# Counters.net
KiCad netlist of a schematic drawn in Altium Designer
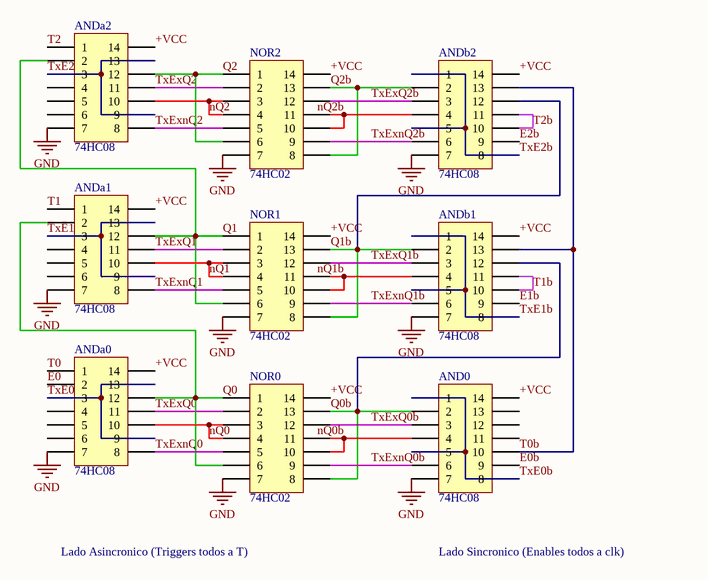
[diagram p0: Counters.SchDoc]

(export (version "E")
  (design (tool "Eeschema 10.0.6"))
  (components
    (comp (ref "AND0") (value "74HC08") (footprint "DIP14") (libsource (lib "LIBEBAL") (part "IC_DIP14")))
    (comp (ref "ANDa0") (value "74HC08") (footprint "DIP14") (libsource (lib "LIBEBAL") (part "IC_DIP14")))
    (comp (ref "ANDa1") (value "74HC08") (footprint "DIP14") (libsource (lib "LIBEBAL") (part "IC_DIP14")))
    (comp (ref "ANDa2") (value "74HC08") (footprint "DIP14") (libsource (lib "LIBEBAL") (part "IC_DIP14")))
    (comp (ref "ANDb1") (value "74HC08") (footprint "DIP14") (libsource (lib "LIBEBAL") (part "IC_DIP14")))
    (comp (ref "ANDb2") (value "74HC08") (footprint "DIP14") (libsource (lib "LIBEBAL") (part "IC_DIP14")))
    (comp (ref "NOR0") (value "74HC02") (footprint "DIP14") (libsource (lib "LIBEBAL") (part "IC_DIP14")))
    (comp (ref "NOR1") (value "74HC02") (footprint "DIP14") (libsource (lib "LIBEBAL") (part "IC_DIP14")))
    (comp (ref "NOR2") (value "74HC02") (footprint "DIP14") (libsource (lib "LIBEBAL") (part "IC_DIP14")))
  )
  (nets
    (net (code "1") (name "/+VCC") (class "Default")
      (node (ref "AND0") (pin "14") (pinfunction "14_14") (pintype "passive"))
      (node (ref "ANDa0") (pin "14") (pinfunction "14_14") (pintype "passive"))
      (node (ref "ANDa1") (pin "14") (pinfunction "14_14") (pintype "passive"))
      (node (ref "ANDa2") (pin "14") (pinfunction "14_14") (pintype "passive"))
      (node (ref "ANDb1") (pin "14") (pinfunction "14_14") (pintype "passive"))
      (node (ref "ANDb2") (pin "14") (pinfunction "14_14") (pintype "passive"))
      (node (ref "NOR0") (pin "14") (pinfunction "14_14") (pintype "passive"))
      (node (ref "NOR1") (pin "14") (pinfunction "14_14") (pintype "passive"))
      (node (ref "NOR2") (pin "14") (pinfunction "14_14") (pintype "passive"))
    )
    (net (code "2") (name "/E0") (class "Default")
      (node (ref "ANDa0") (pin "2") (pinfunction "2_2") (pintype "passive"))
    )
    (net (code "3") (name "/E0b") (class "Default")
      (node (ref "AND0") (pin "9") (pinfunction "9_9") (pintype "passive"))
    )
    (net (code "4") (name "/E1b") (class "Default")
      (node (ref "ANDb1") (pin "9") (pinfunction "9_9") (pintype "passive"))
    )
    (net (code "5") (name "/E2b") (class "Default")
      (node (ref "ANDb2") (pin "9") (pinfunction "9_9") (pintype "passive"))
    )
    (net (code "6") (name "/Q0") (class "Default")
      (node (ref "ANDa0") (pin "12") (pinfunction "12_12") (pintype "passive"))
      (node (ref "ANDa1") (pin "2") (pinfunction "2_2") (pintype "passive"))
      (node (ref "NOR0") (pin "1") (pinfunction "1_1") (pintype "passive"))
      (node (ref "NOR0") (pin "6") (pinfunction "6_6") (pintype "passive"))
    )
    (net (code "7") (name "/Q0b") (class "Default")
      (node (ref "AND0") (pin "2") (pinfunction "2_2") (pintype "passive"))
      (node (ref "ANDb1") (pin "12") (pinfunction "12_12") (pintype "passive"))
      (node (ref "NOR0") (pin "13") (pinfunction "13_13") (pintype "passive"))
      (node (ref "NOR0") (pin "8") (pinfunction "8_8") (pintype "passive"))
    )
    (net (code "8") (name "/Q1") (class "Default")
      (node (ref "ANDa1") (pin "12") (pinfunction "12_12") (pintype "passive"))
      (node (ref "ANDa2") (pin "2") (pinfunction "2_2") (pintype "passive"))
      (node (ref "NOR1") (pin "1") (pinfunction "1_1") (pintype "passive"))
      (node (ref "NOR1") (pin "6") (pinfunction "6_6") (pintype "passive"))
    )
    (net (code "9") (name "/Q1b") (class "Default")
      (node (ref "ANDb1") (pin "2") (pinfunction "2_2") (pintype "passive"))
      (node (ref "ANDb2") (pin "12") (pinfunction "12_12") (pintype "passive"))
      (node (ref "NOR1") (pin "13") (pinfunction "13_13") (pintype "passive"))
      (node (ref "NOR1") (pin "8") (pinfunction "8_8") (pintype "passive"))
    )
    (net (code "10") (name "/Q2") (class "Default")
      (node (ref "ANDa2") (pin "12") (pinfunction "12_12") (pintype "passive"))
      (node (ref "NOR2") (pin "1") (pinfunction "1_1") (pintype "passive"))
      (node (ref "NOR2") (pin "6") (pinfunction "6_6") (pintype "passive"))
    )
    (net (code "11") (name "/Q2b") (class "Default")
      (node (ref "ANDb2") (pin "2") (pinfunction "2_2") (pintype "passive"))
      (node (ref "NOR2") (pin "13") (pinfunction "13_13") (pintype "passive"))
      (node (ref "NOR2") (pin "8") (pinfunction "8_8") (pintype "passive"))
    )
    (net (code "12") (name "/T0") (class "Default")
      (node (ref "ANDa0") (pin "1") (pinfunction "1_1") (pintype "passive"))
    )
    (net (code "13") (name "/T0b") (class "Default")
      (node (ref "AND0") (pin "10") (pinfunction "10_10") (pintype "passive"))
      (node (ref "ANDb1") (pin "13") (pinfunction "13_13") (pintype "passive"))
      (node (ref "ANDb2") (pin "13") (pinfunction "13_13") (pintype "passive"))
    )
    (net (code "14") (name "/T1") (class "Default")
      (node (ref "ANDa1") (pin "1") (pinfunction "1_1") (pintype "passive"))
    )
    (net (code "15") (name "/T1b") (class "Default")
      (node (ref "ANDb1") (pin "10") (pinfunction "10_10") (pintype "passive"))
      (node (ref "ANDb1") (pin "11") (pinfunction "11_11") (pintype "passive"))
    )
    (net (code "16") (name "/T2") (class "Default")
      (node (ref "ANDa2") (pin "1") (pinfunction "1_1") (pintype "passive"))
    )
    (net (code "17") (name "/T2b") (class "Default")
      (node (ref "ANDb2") (pin "10") (pinfunction "10_10") (pintype "passive"))
      (node (ref "ANDb2") (pin "11") (pinfunction "11_11") (pintype "passive"))
    )
    (net (code "18") (name "/TxE0") (class "Default")
      (node (ref "ANDa0") (pin "13") (pinfunction "13_13") (pintype "passive"))
      (node (ref "ANDa0") (pin "3") (pinfunction "3_3") (pintype "passive"))
      (node (ref "ANDa0") (pin "9") (pinfunction "9_9") (pintype "passive"))
    )
    (net (code "19") (name "/TxE0b") (class "Default")
      (node (ref "AND0") (pin "1") (pinfunction "1_1") (pintype "passive"))
      (node (ref "AND0") (pin "5") (pinfunction "5_5") (pintype "passive"))
      (node (ref "AND0") (pin "8") (pinfunction "8_8") (pintype "passive"))
    )
    (net (code "20") (name "/TxE1") (class "Default")
      (node (ref "ANDa1") (pin "13") (pinfunction "13_13") (pintype "passive"))
      (node (ref "ANDa1") (pin "3") (pinfunction "3_3") (pintype "passive"))
      (node (ref "ANDa1") (pin "9") (pinfunction "9_9") (pintype "passive"))
    )
    (net (code "21") (name "/TxE1b") (class "Default")
      (node (ref "ANDb1") (pin "1") (pinfunction "1_1") (pintype "passive"))
      (node (ref "ANDb1") (pin "5") (pinfunction "5_5") (pintype "passive"))
      (node (ref "ANDb1") (pin "8") (pinfunction "8_8") (pintype "passive"))
    )
    (net (code "22") (name "/TxE2") (class "Default")
      (node (ref "ANDa2") (pin "13") (pinfunction "13_13") (pintype "passive"))
      (node (ref "ANDa2") (pin "3") (pinfunction "3_3") (pintype "passive"))
      (node (ref "ANDa2") (pin "9") (pinfunction "9_9") (pintype "passive"))
    )
    (net (code "23") (name "/TxE2b") (class "Default")
      (node (ref "ANDb2") (pin "1") (pinfunction "1_1") (pintype "passive"))
      (node (ref "ANDb2") (pin "5") (pinfunction "5_5") (pintype "passive"))
      (node (ref "ANDb2") (pin "8") (pinfunction "8_8") (pintype "passive"))
    )
    (net (code "24") (name "/TxExQ0") (class "Default")
      (node (ref "ANDa0") (pin "11") (pinfunction "11_11") (pintype "passive"))
      (node (ref "NOR0") (pin "2") (pinfunction "2_2") (pintype "passive"))
    )
    (net (code "25") (name "/TxExQ0b") (class "Default")
      (node (ref "AND0") (pin "3") (pinfunction "3_3") (pintype "passive"))
      (node (ref "NOR0") (pin "12") (pinfunction "12_12") (pintype "passive"))
    )
    (net (code "26") (name "/TxExQ1") (class "Default")
      (node (ref "ANDa1") (pin "11") (pinfunction "11_11") (pintype "passive"))
      (node (ref "NOR1") (pin "2") (pinfunction "2_2") (pintype "passive"))
    )
    (net (code "27") (name "/TxExQ1b") (class "Default")
      (node (ref "ANDb1") (pin "3") (pinfunction "3_3") (pintype "passive"))
      (node (ref "NOR1") (pin "12") (pinfunction "12_12") (pintype "passive"))
    )
    (net (code "28") (name "/TxExQ2") (class "Default")
      (node (ref "ANDa2") (pin "11") (pinfunction "11_11") (pintype "passive"))
      (node (ref "NOR2") (pin "2") (pinfunction "2_2") (pintype "passive"))
    )
    (net (code "29") (name "/TxExQ2b") (class "Default")
      (node (ref "ANDb2") (pin "3") (pinfunction "3_3") (pintype "passive"))
      (node (ref "NOR2") (pin "12") (pinfunction "12_12") (pintype "passive"))
    )
    (net (code "30") (name "/TxExnQ0") (class "Default")
      (node (ref "ANDa0") (pin "8") (pinfunction "8_8") (pintype "passive"))
      (node (ref "NOR0") (pin "5") (pinfunction "5_5") (pintype "passive"))
    )
    (net (code "31") (name "/TxExnQ0b") (class "Default")
      (node (ref "AND0") (pin "6") (pinfunction "6_6") (pintype "passive"))
      (node (ref "NOR0") (pin "9") (pinfunction "9_9") (pintype "passive"))
    )
    (net (code "32") (name "/TxExnQ1") (class "Default")
      (node (ref "ANDa1") (pin "8") (pinfunction "8_8") (pintype "passive"))
      (node (ref "NOR1") (pin "5") (pinfunction "5_5") (pintype "passive"))
    )
    (net (code "33") (name "/TxExnQ1b") (class "Default")
      (node (ref "ANDb1") (pin "6") (pinfunction "6_6") (pintype "passive"))
      (node (ref "NOR1") (pin "9") (pinfunction "9_9") (pintype "passive"))
    )
    (net (code "34") (name "/TxExnQ2") (class "Default")
      (node (ref "ANDa2") (pin "8") (pinfunction "8_8") (pintype "passive"))
      (node (ref "NOR2") (pin "5") (pinfunction "5_5") (pintype "passive"))
    )
    (net (code "35") (name "/TxExnQ2b") (class "Default")
      (node (ref "ANDb2") (pin "6") (pinfunction "6_6") (pintype "passive"))
      (node (ref "NOR2") (pin "9") (pinfunction "9_9") (pintype "passive"))
    )
    (net (code "36") (name "/nQ0") (class "Default")
      (node (ref "ANDa0") (pin "10") (pinfunction "10_10") (pintype "passive"))
      (node (ref "NOR0") (pin "3") (pinfunction "3_3") (pintype "passive"))
      (node (ref "NOR0") (pin "4") (pinfunction "4_4") (pintype "passive"))
    )
    (net (code "38") (name "/nQ1") (class "Default")
      (node (ref "ANDa1") (pin "10") (pinfunction "10_10") (pintype "passive"))
      (node (ref "NOR1") (pin "3") (pinfunction "3_3") (pintype "passive"))
      (node (ref "NOR1") (pin "4") (pinfunction "4_4") (pintype "passive"))
    )
    (net (code "40") (name "/nQ2") (class "Default")
      (node (ref "ANDa2") (pin "10") (pinfunction "10_10") (pintype "passive"))
      (node (ref "NOR2") (pin "3") (pinfunction "3_3") (pintype "passive"))
      (node (ref "NOR2") (pin "4") (pinfunction "4_4") (pintype "passive"))
    )
    (net (code "42") (name "GND") (class "Default")
      (node (ref "AND0") (pin "7") (pinfunction "7_7") (pintype "passive"))
      (node (ref "ANDa0") (pin "7") (pinfunction "7_7") (pintype "passive"))
      (node (ref "ANDa1") (pin "7") (pinfunction "7_7") (pintype "passive"))
      (node (ref "ANDa2") (pin "7") (pinfunction "7_7") (pintype "passive"))
      (node (ref "ANDb1") (pin "7") (pinfunction "7_7") (pintype "passive"))
      (node (ref "ANDb2") (pin "7") (pinfunction "7_7") (pintype "passive"))
      (node (ref "NOR0") (pin "7") (pinfunction "7_7") (pintype "passive"))
      (node (ref "NOR1") (pin "7") (pinfunction "7_7") (pintype "passive"))
      (node (ref "NOR2") (pin "7") (pinfunction "7_7") (pintype "passive"))
    )
    (net (code "43") (name "Net-(AND0-Pad4)") (class "Default")
      (node (ref "AND0") (pin "4") (pinfunction "4_4") (pintype "passive"))
      (node (ref "NOR0") (pin "10") (pinfunction "10_10") (pintype "passive"))
      (node (ref "NOR0") (pin "11") (pinfunction "11_11") (pintype "passive"))
    )
    (net (code "44") (name "Net-(ANDb1-Pad4)") (class "Default")
      (node (ref "ANDb1") (pin "4") (pinfunction "4_4") (pintype "passive"))
      (node (ref "NOR1") (pin "10") (pinfunction "10_10") (pintype "passive"))
      (node (ref "NOR1") (pin "11") (pinfunction "11_11") (pintype "passive"))
    )
    (net (code "45") (name "Net-(ANDb2-Pad4)") (class "Default")
      (node (ref "ANDb2") (pin "4") (pinfunction "4_4") (pintype "passive"))
      (node (ref "NOR2") (pin "10") (pinfunction "10_10") (pintype "passive"))
      (node (ref "NOR2") (pin "11") (pinfunction "11_11") (pintype "passive"))
    )
    (net (code "46") (name "unconnected-(AND0-Pad11)") (class "Default")
      (node (ref "AND0") (pin "11") (pinfunction "11_11") (pintype "passive"))
    )
    (net (code "47") (name "unconnected-(AND0-Pad12)") (class "Default")
      (node (ref "AND0") (pin "12") (pinfunction "12_12") (pintype "passive"))
    )
    (net (code "48") (name "unconnected-(AND0-Pad13)") (class "Default")
      (node (ref "AND0") (pin "13") (pinfunction "13_13") (pintype "passive"))
    )
    (net (code "49") (name "unconnected-(ANDa0-Pad4)") (class "Default")
      (node (ref "ANDa0") (pin "4") (pinfunction "4_4") (pintype "passive"))
    )
    (net (code "50") (name "unconnected-(ANDa0-Pad5)") (class "Default")
      (node (ref "ANDa0") (pin "5") (pinfunction "5_5") (pintype "passive"))
    )
    (net (code "51") (name "unconnected-(ANDa0-Pad6)") (class "Default")
      (node (ref "ANDa0") (pin "6") (pinfunction "6_6") (pintype "passive"))
    )
    (net (code "52") (name "unconnected-(ANDa1-Pad4)") (class "Default")
      (node (ref "ANDa1") (pin "4") (pinfunction "4_4") (pintype "passive"))
    )
    (net (code "53") (name "unconnected-(ANDa1-Pad5)") (class "Default")
      (node (ref "ANDa1") (pin "5") (pinfunction "5_5") (pintype "passive"))
    )
    (net (code "54") (name "unconnected-(ANDa1-Pad6)") (class "Default")
      (node (ref "ANDa1") (pin "6") (pinfunction "6_6") (pintype "passive"))
    )
    (net (code "55") (name "unconnected-(ANDa2-Pad4)") (class "Default")
      (node (ref "ANDa2") (pin "4") (pinfunction "4_4") (pintype "passive"))
    )
    (net (code "56") (name "unconnected-(ANDa2-Pad5)") (class "Default")
      (node (ref "ANDa2") (pin "5") (pinfunction "5_5") (pintype "passive"))
    )
    (net (code "57") (name "unconnected-(ANDa2-Pad6)") (class "Default")
      (node (ref "ANDa2") (pin "6") (pinfunction "6_6") (pintype "passive"))
    )
  )
)
